# SCH_Pedal-Pcb-v3-different-batch_2024-05.net
KiCad netlist of a schematic drawn in EasyEDA
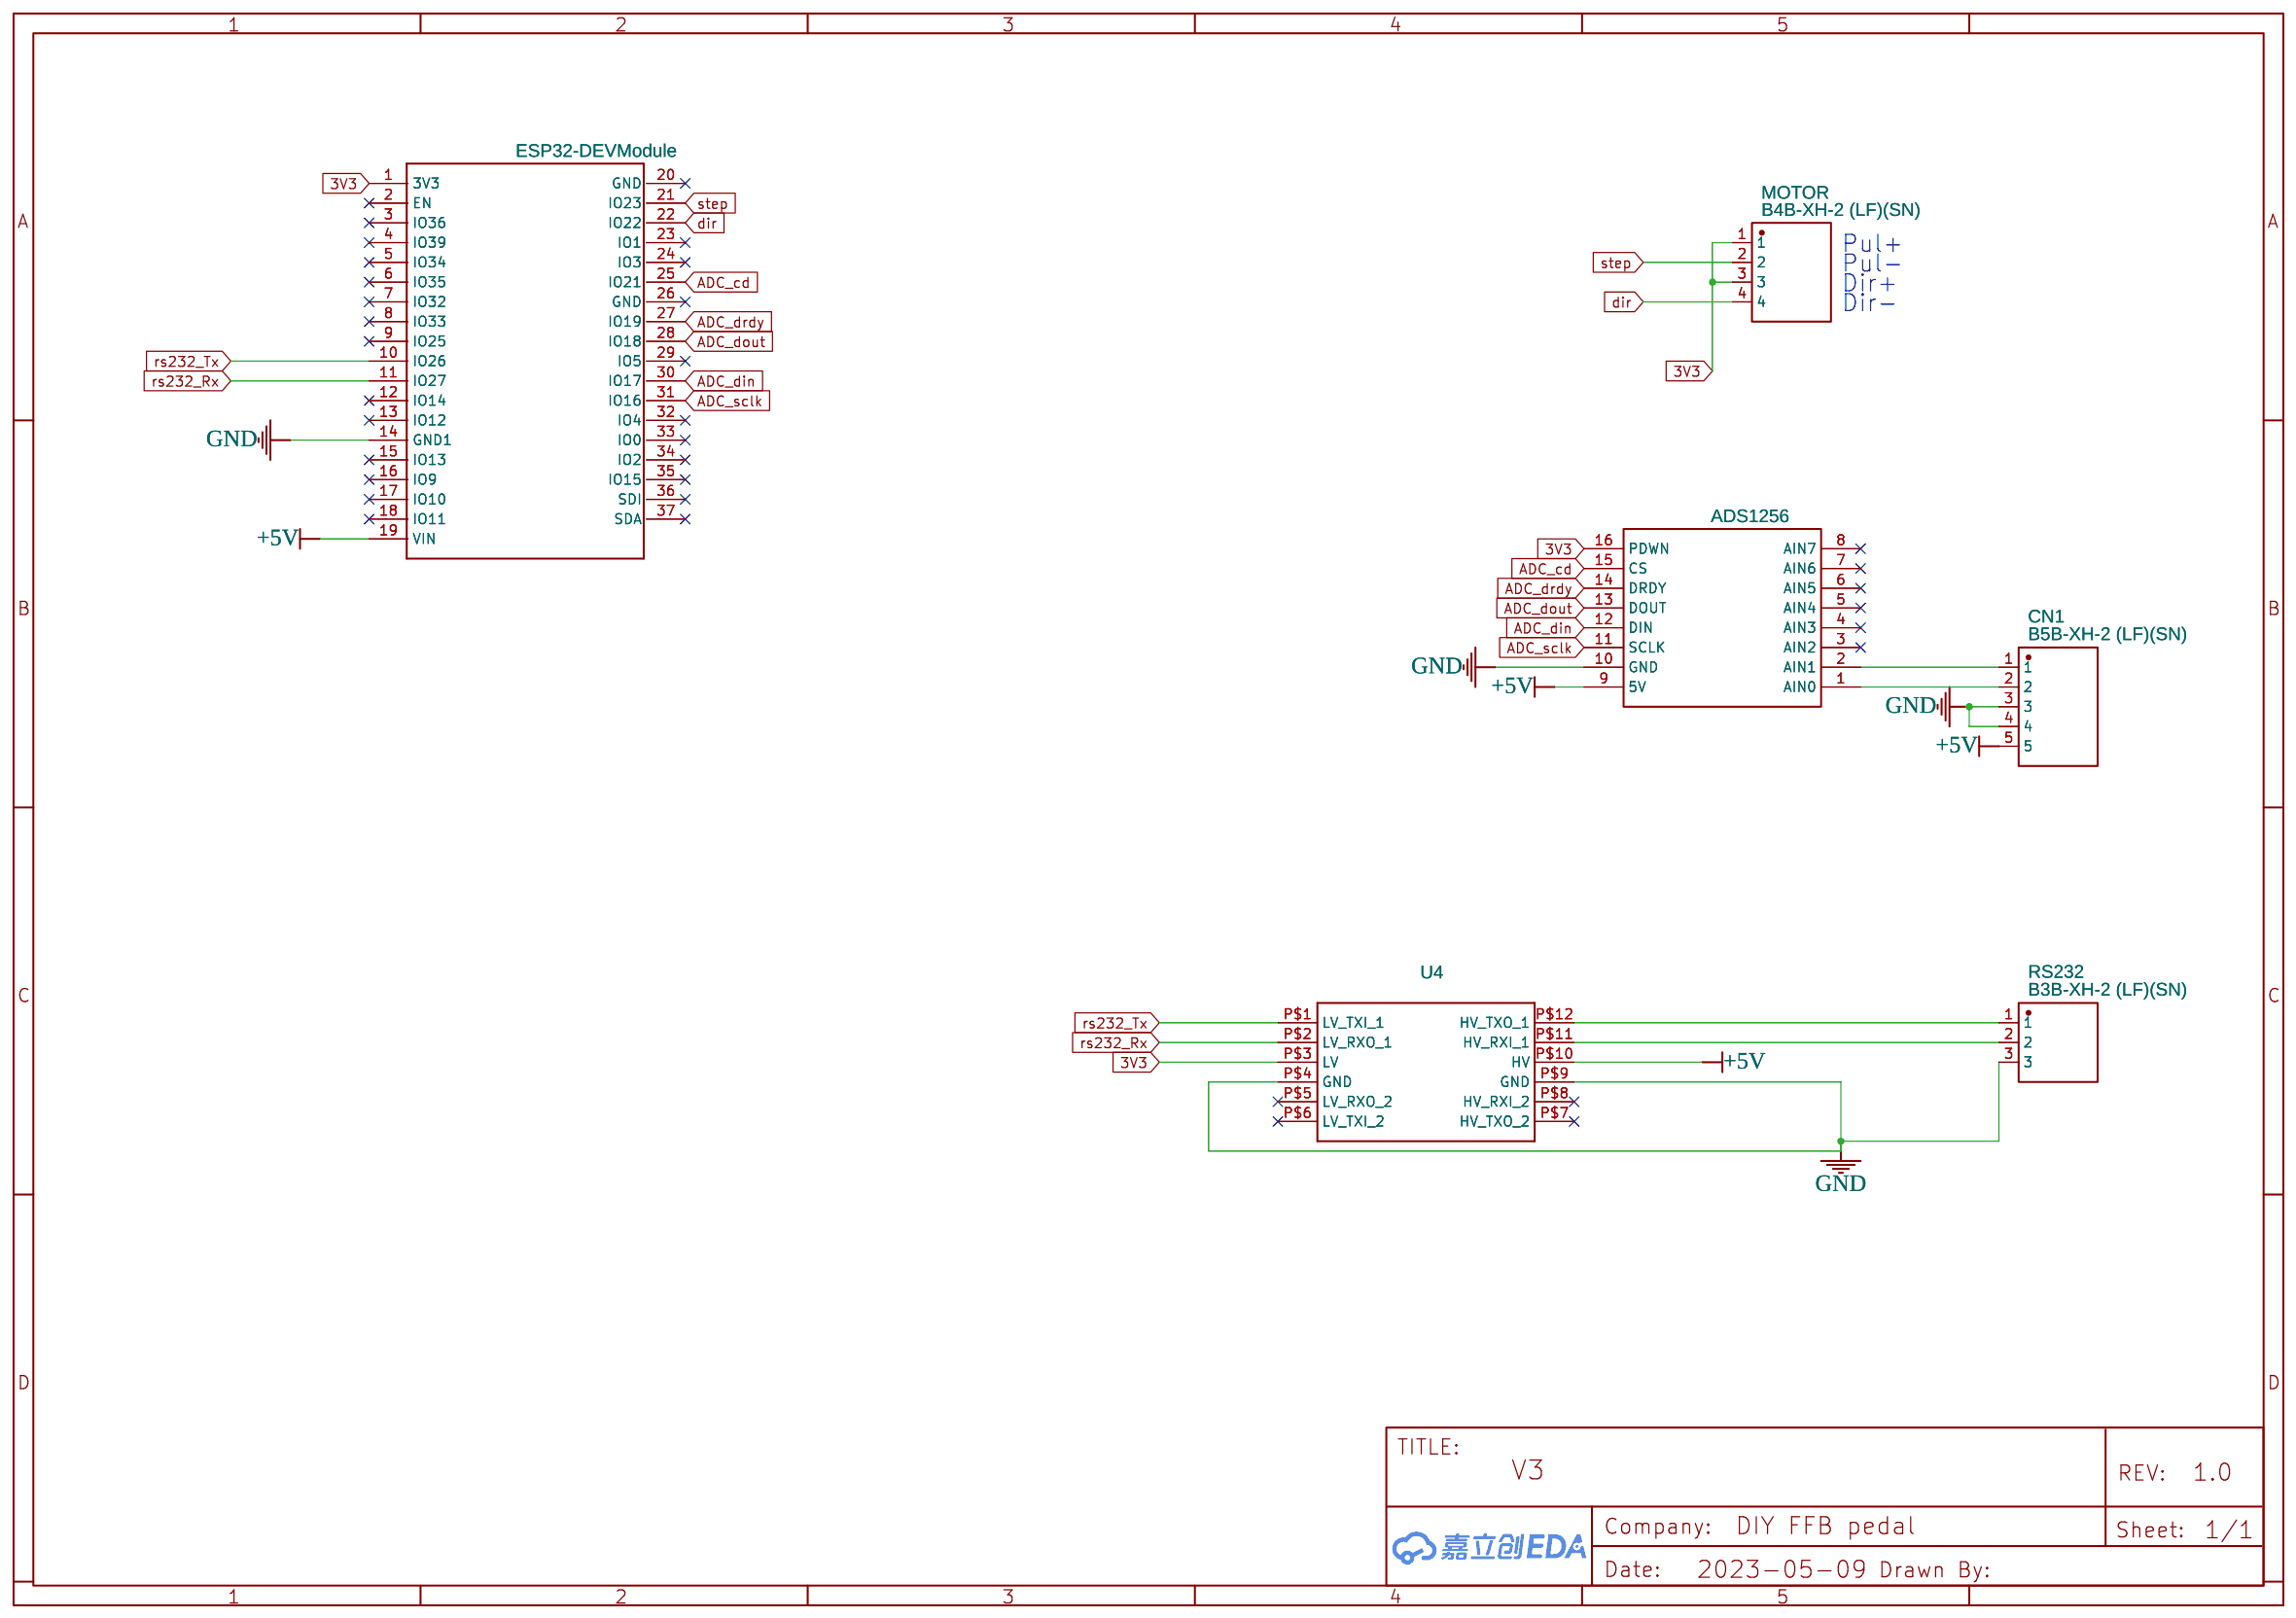
[diagram p0: schematic sheet]

(export (version "E")
  (design (tool "Eeschema 10.0.6"))
  (components
    (comp (ref "CN1")
      (value "B5B-XH-2 (LF)(SN)")
      (fields (field (name "Manufacturer Part") "B5B-XH-2(LF)(SN)") (field (name "Manufacturer") "JST"))
      (libsource (lib "") (part "B5B-XH-2 (LF)(SN)"))
    )
    (comp (ref "MOTOR")
      (value "B4B-XH-2 (LF)(SN)")
      (fields (field (name "Manufacturer Part") "B4B-XH-2(LF)(SN)") (field (name "Manufacturer") "JST"))
      (libsource (lib "") (part "B4B-XH-2 (LF)(SN)"))
    )
    (comp (ref "RS232")
      (value "B3B-XH-2 (LF)(SN)")
      (fields (field (name "Manufacturer Part") "B3B-XH-2(LF)(SN)") (field (name "Manufacturer") "JST"))
      (libsource (lib "") (part "B3B-XH-2 (LF)(SN)"))
    )
    (comp (ref "U3") (value "ADS1256") (libsource (lib "") (part "ADS1256")))
    (comp (ref "U4") (value "NO") (libsource (lib "") (part "LOGIC_LEVEL_CONVERTER")))
    (comp (ref "U5") (value "ESP32-DEVModule") (libsource (lib "") (part "ESP32-DEVModule")))
  )
  (nets
    (net (code "1") (name "+5V") (class "Default")
      (node (ref "CN1") (pin "5") (pinfunction "5_5") (pintype "unspecified"))
      (node (ref "U3") (pin "9") (pinfunction "5V_9") (pintype "unspecified"))
      (node (ref "U4") (pin "P$10") (pinfunction "HV_P$10") (pintype "unspecified"))
      (node (ref "U5") (pin "19") (pinfunction "VIN_19") (pintype "bidirectional"))
    )
    (net (code "2") (name "3V3") (class "Default")
      (node (ref "MOTOR") (pin "1") (pinfunction "1_1") (pintype "unspecified"))
      (node (ref "MOTOR") (pin "3") (pinfunction "3_3") (pintype "unspecified"))
      (node (ref "U3") (pin "16") (pinfunction "PDWN_16") (pintype "unspecified"))
      (node (ref "U4") (pin "P$3") (pinfunction "LV_P$3") (pintype "unspecified"))
      (node (ref "U5") (pin "1") (pinfunction "3V3_1") (pintype "bidirectional"))
    )
    (net (code "3") (name "ADC_cd") (class "Default")
      (node (ref "U3") (pin "15") (pinfunction "CS_15") (pintype "unspecified"))
      (node (ref "U5") (pin "25") (pinfunction "IO21_25") (pintype "bidirectional"))
    )
    (net (code "4") (name "ADC_din") (class "Default")
      (node (ref "U3") (pin "12") (pinfunction "DIN_12") (pintype "unspecified"))
      (node (ref "U5") (pin "30") (pinfunction "IO17_30") (pintype "bidirectional"))
    )
    (net (code "5") (name "ADC_dout") (class "Default")
      (node (ref "U3") (pin "13") (pinfunction "DOUT_13") (pintype "unspecified"))
      (node (ref "U5") (pin "28") (pinfunction "IO18_28") (pintype "bidirectional"))
    )
    (net (code "6") (name "ADC_drdy") (class "Default")
      (node (ref "U3") (pin "14") (pinfunction "DRDY_14") (pintype "unspecified"))
      (node (ref "U5") (pin "27") (pinfunction "IO19_27") (pintype "bidirectional"))
    )
    (net (code "7") (name "ADC_sclk") (class "Default")
      (node (ref "U3") (pin "11") (pinfunction "SCLK_11") (pintype "unspecified"))
      (node (ref "U5") (pin "31") (pinfunction "IO16_31") (pintype "bidirectional"))
    )
    (net (code "8") (name "GND") (class "Default")
      (node (ref "CN1") (pin "3") (pinfunction "3_3") (pintype "unspecified"))
      (node (ref "CN1") (pin "4") (pinfunction "4_4") (pintype "unspecified"))
      (node (ref "RS232") (pin "3") (pinfunction "3_3") (pintype "unspecified"))
      (node (ref "U3") (pin "10") (pinfunction "GND_10") (pintype "unspecified"))
      (node (ref "U4") (pin "P$4") (pinfunction "GND_P$4") (pintype "unspecified"))
      (node (ref "U4") (pin "P$9") (pinfunction "GND_P$9") (pintype "unspecified"))
      (node (ref "U5") (pin "14") (pinfunction "GND1_14") (pintype "bidirectional"))
    )
    (net (code "9") (name "Net-(U3-AIN0)") (class "Default")
      (node (ref "CN1") (pin "2") (pinfunction "2_2") (pintype "unspecified"))
      (node (ref "U3") (pin "1") (pinfunction "AIN0_1") (pintype "unspecified"))
    )
    (net (code "10") (name "Net-(U3-AIN1)") (class "Default")
      (node (ref "CN1") (pin "1") (pinfunction "1_1") (pintype "unspecified"))
      (node (ref "U3") (pin "2") (pinfunction "AIN1_2") (pintype "unspecified"))
    )
    (net (code "11") (name "Net-(U4-HV_RXI_1)") (class "Default")
      (node (ref "RS232") (pin "2") (pinfunction "2_2") (pintype "unspecified"))
      (node (ref "U4") (pin "P$11") (pinfunction "HV_RXI_1_P$11") (pintype "unspecified"))
    )
    (net (code "12") (name "Net-(U4-HV_TXO_1)") (class "Default")
      (node (ref "RS232") (pin "1") (pinfunction "1_1") (pintype "unspecified"))
      (node (ref "U4") (pin "P$12") (pinfunction "HV_TXO_1_P$12") (pintype "unspecified"))
    )
    (net (code "13") (name "dir") (class "Default")
      (node (ref "MOTOR") (pin "4") (pinfunction "4_4") (pintype "unspecified"))
      (node (ref "U5") (pin "22") (pinfunction "IO22_22") (pintype "bidirectional"))
    )
    (net (code "14") (name "rs232_Rx") (class "Default")
      (node (ref "U4") (pin "P$2") (pinfunction "LV_RXO_1_P$2") (pintype "unspecified"))
      (node (ref "U5") (pin "11") (pinfunction "IO27_11") (pintype "bidirectional"))
    )
    (net (code "15") (name "rs232_Tx") (class "Default")
      (node (ref "U4") (pin "P$1") (pinfunction "LV_TXI_1_P$1") (pintype "unspecified"))
      (node (ref "U5") (pin "10") (pinfunction "IO26_10") (pintype "bidirectional"))
    )
    (net (code "16") (name "step") (class "Default")
      (node (ref "MOTOR") (pin "2") (pinfunction "2_2") (pintype "unspecified"))
      (node (ref "U5") (pin "21") (pinfunction "IO23_21") (pintype "bidirectional"))
    )
    (net (code "17") (name "unconnected-(U3-AIN2-Pad3)") (class "Default")
      (node (ref "U3") (pin "3") (pinfunction "AIN2_3") (pintype "unspecified+no_connect"))
    )
    (net (code "18") (name "unconnected-(U3-AIN3-Pad4)") (class "Default")
      (node (ref "U3") (pin "4") (pinfunction "AIN3_4") (pintype "unspecified+no_connect"))
    )
    (net (code "19") (name "unconnected-(U3-AIN4-Pad5)") (class "Default")
      (node (ref "U3") (pin "5") (pinfunction "AIN4_5") (pintype "unspecified+no_connect"))
    )
    (net (code "20") (name "unconnected-(U3-AIN5-Pad6)") (class "Default")
      (node (ref "U3") (pin "6") (pinfunction "AIN5_6") (pintype "unspecified+no_connect"))
    )
    (net (code "21") (name "unconnected-(U3-AIN6-Pad7)") (class "Default")
      (node (ref "U3") (pin "7") (pinfunction "AIN6_7") (pintype "unspecified+no_connect"))
    )
    (net (code "22") (name "unconnected-(U3-AIN7-Pad8)") (class "Default")
      (node (ref "U3") (pin "8") (pinfunction "AIN7_8") (pintype "unspecified+no_connect"))
    )
    (net (code "23") (name "unconnected-(U4-HV_RXI_2-PadP$8)") (class "Default")
      (node (ref "U4") (pin "P$8") (pinfunction "HV_RXI_2_P$8") (pintype "unspecified+no_connect"))
    )
    (net (code "24") (name "unconnected-(U4-HV_TXO_2-PadP$7)") (class "Default")
      (node (ref "U4") (pin "P$7") (pinfunction "HV_TXO_2_P$7") (pintype "unspecified+no_connect"))
    )
    (net (code "25") (name "unconnected-(U4-LV_RXO_2-PadP$5)") (class "Default")
      (node (ref "U4") (pin "P$5") (pinfunction "LV_RXO_2_P$5") (pintype "unspecified+no_connect"))
    )
    (net (code "26") (name "unconnected-(U4-LV_TXI_2-PadP$6)") (class "Default")
      (node (ref "U4") (pin "P$6") (pinfunction "LV_TXI_2_P$6") (pintype "unspecified+no_connect"))
    )
    (net (code "27") (name "unconnected-(U5-EN-Pad2)") (class "Default")
      (node (ref "U5") (pin "2") (pinfunction "EN_2") (pintype "bidirectional+no_connect"))
    )
    (net (code "28") (name "unconnected-(U5-GND-Pad20)") (class "Default")
      (node (ref "U5") (pin "20") (pinfunction "GND_20") (pintype "bidirectional+no_connect"))
    )
    (net (code "29") (name "unconnected-(U5-GND-Pad26)") (class "Default")
      (node (ref "U5") (pin "26") (pinfunction "GND_26") (pintype "bidirectional+no_connect"))
    )
    (net (code "30") (name "unconnected-(U5-IO0-Pad33)") (class "Default")
      (node (ref "U5") (pin "33") (pinfunction "IO0_33") (pintype "bidirectional+no_connect"))
    )
    (net (code "31") (name "unconnected-(U5-IO1-Pad23)") (class "Default")
      (node (ref "U5") (pin "23") (pinfunction "IO1_23") (pintype "bidirectional+no_connect"))
    )
    (net (code "32") (name "unconnected-(U5-IO2-Pad34)") (class "Default")
      (node (ref "U5") (pin "34") (pinfunction "IO2_34") (pintype "bidirectional+no_connect"))
    )
    (net (code "33") (name "unconnected-(U5-IO3-Pad24)") (class "Default")
      (node (ref "U5") (pin "24") (pinfunction "IO3_24") (pintype "bidirectional+no_connect"))
    )
    (net (code "34") (name "unconnected-(U5-IO4-Pad32)") (class "Default")
      (node (ref "U5") (pin "32") (pinfunction "IO4_32") (pintype "bidirectional+no_connect"))
    )
    (net (code "35") (name "unconnected-(U5-IO5-Pad29)") (class "Default")
      (node (ref "U5") (pin "29") (pinfunction "IO5_29") (pintype "bidirectional+no_connect"))
    )
    (net (code "36") (name "unconnected-(U5-IO9-Pad16)") (class "Default")
      (node (ref "U5") (pin "16") (pinfunction "IO9_16") (pintype "bidirectional+no_connect"))
    )
    (net (code "37") (name "unconnected-(U5-IO10-Pad17)") (class "Default")
      (node (ref "U5") (pin "17") (pinfunction "IO10_17") (pintype "bidirectional+no_connect"))
    )
    (net (code "38") (name "unconnected-(U5-IO11-Pad18)") (class "Default")
      (node (ref "U5") (pin "18") (pinfunction "IO11_18") (pintype "bidirectional+no_connect"))
    )
    (net (code "39") (name "unconnected-(U5-IO12-Pad13)") (class "Default")
      (node (ref "U5") (pin "13") (pinfunction "IO12_13") (pintype "bidirectional+no_connect"))
    )
    (net (code "40") (name "unconnected-(U5-IO13-Pad15)") (class "Default")
      (node (ref "U5") (pin "15") (pinfunction "IO13_15") (pintype "bidirectional+no_connect"))
    )
    (net (code "41") (name "unconnected-(U5-IO14-Pad12)") (class "Default")
      (node (ref "U5") (pin "12") (pinfunction "IO14_12") (pintype "bidirectional+no_connect"))
    )
    (net (code "42") (name "unconnected-(U5-IO15-Pad35)") (class "Default")
      (node (ref "U5") (pin "35") (pinfunction "IO15_35") (pintype "bidirectional+no_connect"))
    )
    (net (code "43") (name "unconnected-(U5-IO25-Pad9)") (class "Default")
      (node (ref "U5") (pin "9") (pinfunction "IO25_9") (pintype "bidirectional+no_connect"))
    )
    (net (code "44") (name "unconnected-(U5-IO32-Pad7)") (class "Default")
      (node (ref "U5") (pin "7") (pinfunction "IO32_7") (pintype "bidirectional+no_connect"))
    )
    (net (code "45") (name "unconnected-(U5-IO33-Pad8)") (class "Default")
      (node (ref "U5") (pin "8") (pinfunction "IO33_8") (pintype "bidirectional+no_connect"))
    )
    (net (code "46") (name "unconnected-(U5-IO34-Pad5)") (class "Default")
      (node (ref "U5") (pin "5") (pinfunction "IO34_5") (pintype "bidirectional+no_connect"))
    )
    (net (code "47") (name "unconnected-(U5-IO35-Pad6)") (class "Default")
      (node (ref "U5") (pin "6") (pinfunction "IO35_6") (pintype "bidirectional+no_connect"))
    )
    (net (code "48") (name "unconnected-(U5-IO36-Pad3)") (class "Default")
      (node (ref "U5") (pin "3") (pinfunction "IO36_3") (pintype "bidirectional+no_connect"))
    )
    (net (code "49") (name "unconnected-(U5-IO39-Pad4)") (class "Default")
      (node (ref "U5") (pin "4") (pinfunction "IO39_4") (pintype "bidirectional+no_connect"))
    )
    (net (code "50") (name "unconnected-(U5-SDA-Pad37)") (class "Default")
      (node (ref "U5") (pin "37") (pinfunction "SDA_37") (pintype "bidirectional+no_connect"))
    )
    (net (code "51") (name "unconnected-(U5-SDI-Pad36)") (class "Default")
      (node (ref "U5") (pin "36") (pinfunction "SDI_36") (pintype "bidirectional+no_connect"))
    )
  )
)
